# POWER_Manegement.net
KiCad netlist of a schematic drawn in Altium Designer
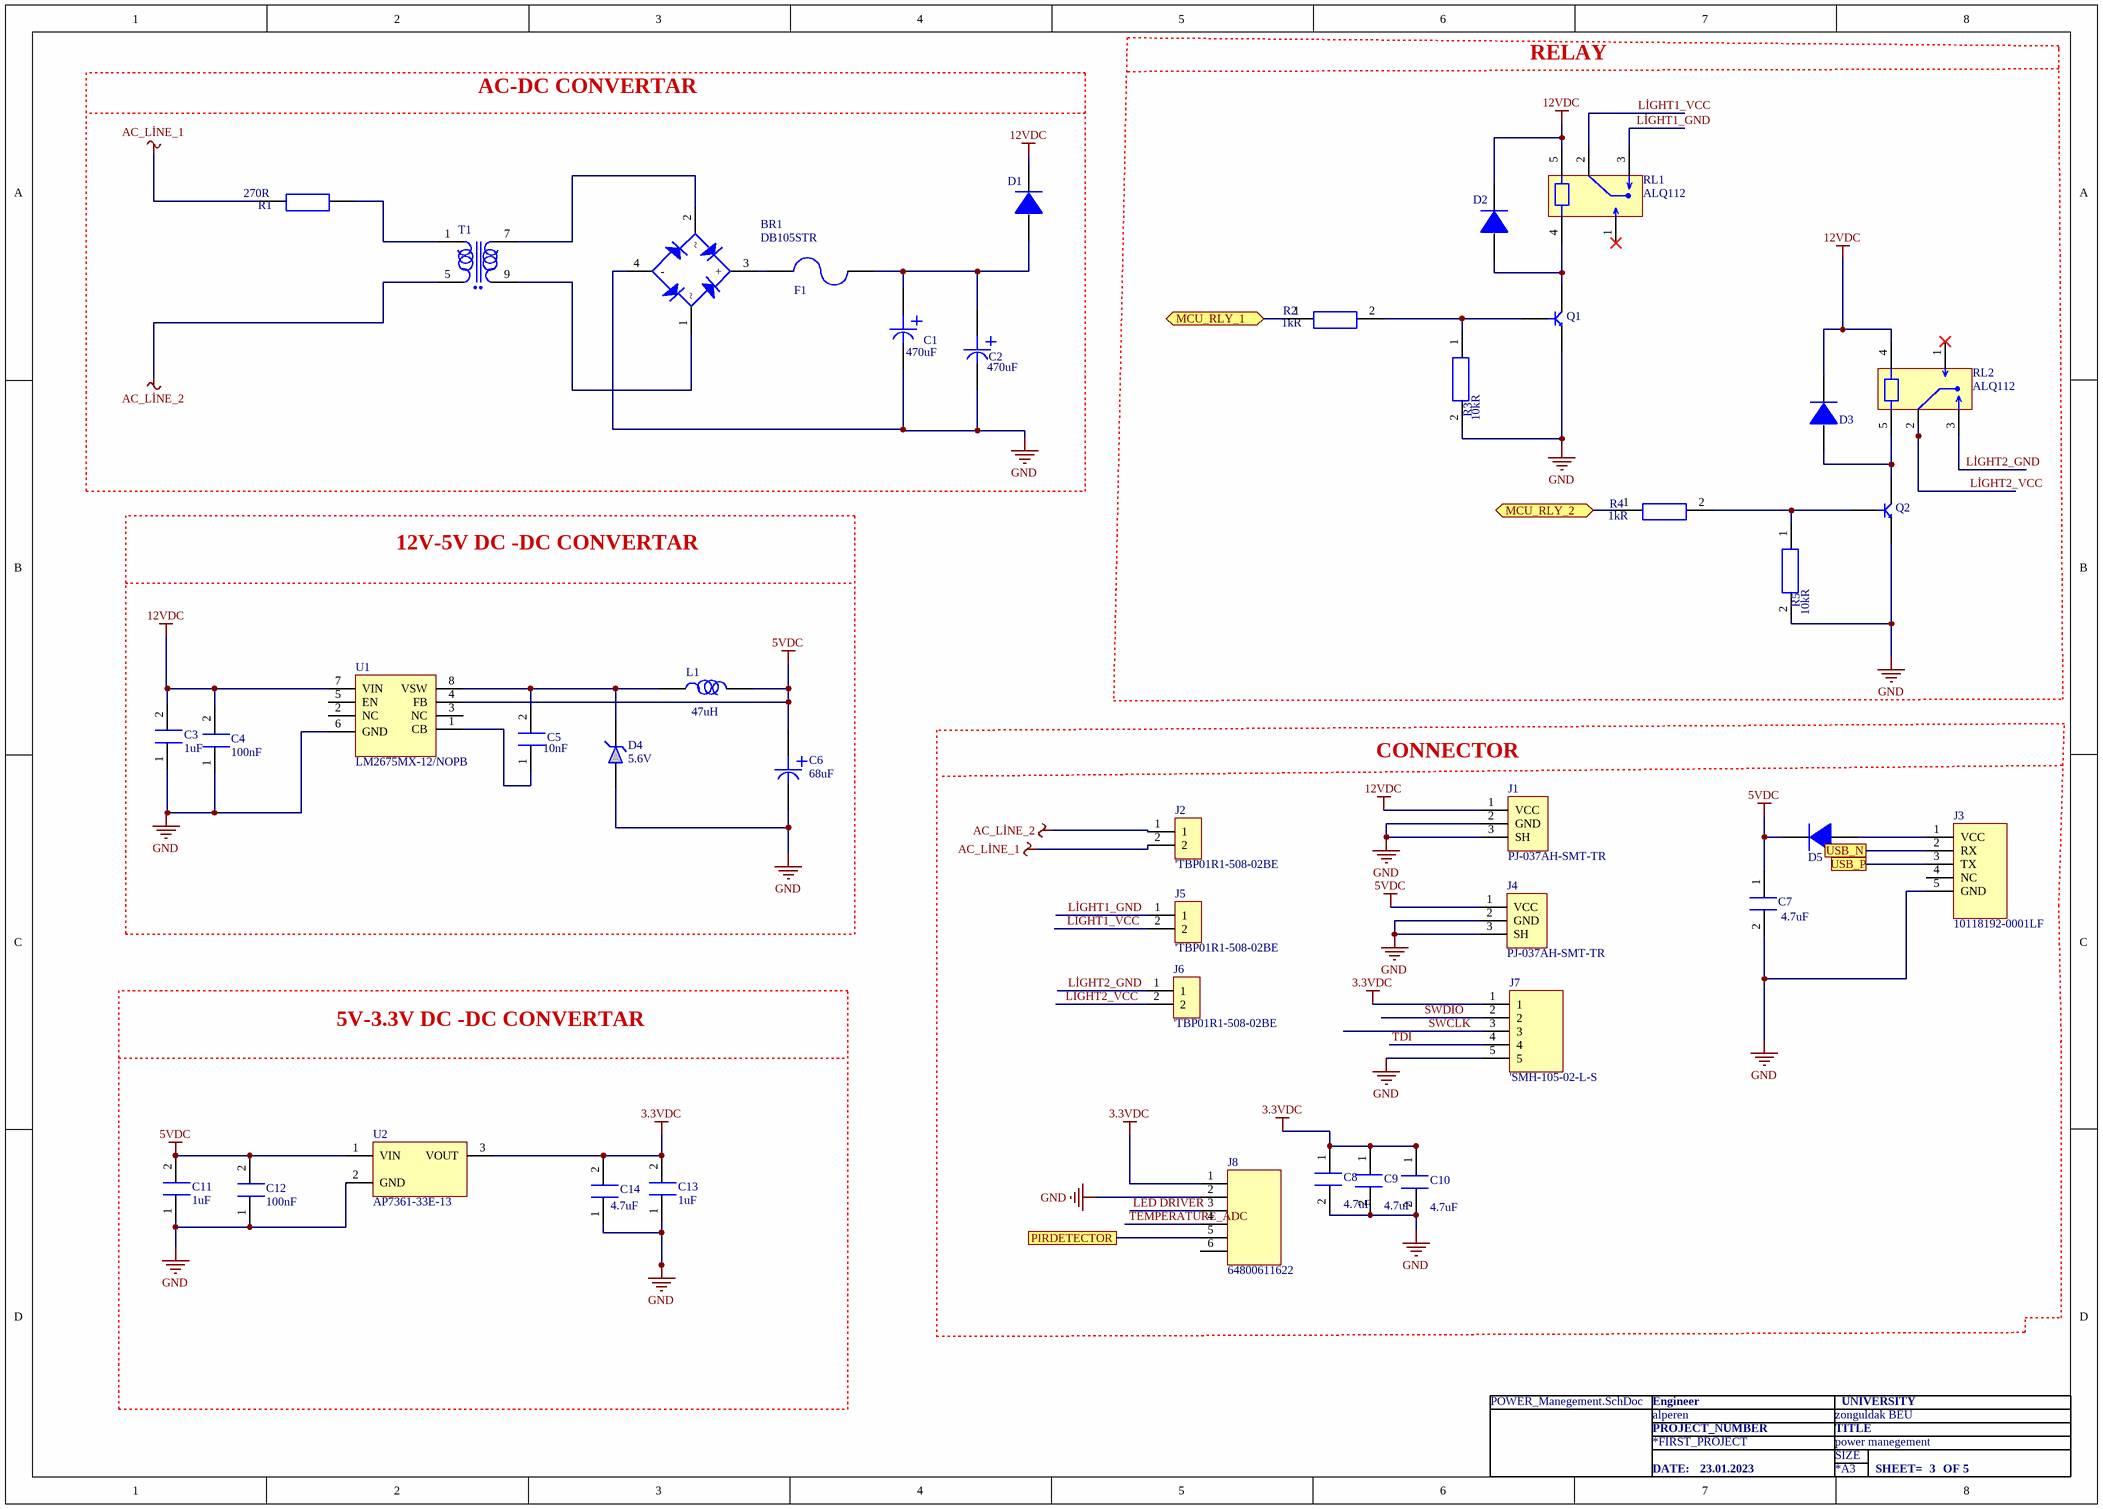
[diagram p0: POWER_Manegement.SchDoc]

(export (version "E")
  (design (tool "Eeschema 10.0.6"))
  (components
    (comp (ref "BR1")
      (value "DB105STR")
      (footprint "DB105STR")
      (description "Bridge Rect 1PHASE 600V 1A Db-s")
      (fields
        (field (name "MANUFACTURER") "Sangdest Microelectronics")
        (field (name "MANUFACTURER PART NUMBER") "DB105S")
      )
      (libsource (lib "first_project_library") (part "DB105STR"))
    )
    (comp (ref "C1")
      (value "ESH477M050AH4AA")
      (footprint "CAP_RADIAL_D10_P5")
      (description "Cap, 470UF, 50V, Alu Elec, Radial")
      (fields
        (field (name "MANUFACTURER") "KEMET")
        (field (name "TOLERANCE") "20%")
        (field (name "CAPACITANCE") "470uF")
      )
      (libsource (lib "first_project_library") (part "ESH477M050AH4AA"))
    )
    (comp (ref "C2")
      (value "ESH477M050AH4AA")
      (footprint "CAP_RADIAL_D10_P5")
      (description "Cap, 470UF, 50V, Alu Elec, Radial")
      (fields
        (field (name "MANUFACTURER") "KEMET")
        (field (name "TOLERANCE") "20%")
        (field (name "CAPACITANCE") "470uF")
      )
      (libsource (lib "first_project_library") (part "ESH477M050AH4AA"))
    )
    (comp (ref "C3")
      (value "CAP CER 1UF 0805")
      (footprint "CAP_0805")
      (description "CAP CER 1UF 25V X5R 0805")
      (fields
        (field (name "MANUFACTURER") "Murata")
        (field (name "MANUFACTURER PART NUMBER") "GRM216R61E105KA12D")
        (field (name "CAPACITANCE") "1uF")
      )
      (libsource (lib "first_project_library") (part "CAP CER 1UF 0805"))
    )
    (comp (ref "C4")
      (value "CAP CF 100NF 0805")
      (footprint "CAP_0805")
      (description "CAP CER 0.1UF 50V X7R 0805")
      (fields
        (field (name "MANUFACTURER") "Samsung")
        (field (name "MANUFACTURER PART NUMBER") "CL21B104KBCNNNC")
        (field (name "CAPACITANCE") "100nF")
      )
      (libsource (lib "first_project_library") (part "CAP CF 100NF 0805"))
    )
    (comp (ref "C5")
      (value "CAP CER 10nF 0603")
      (footprint "CAP_0603")
      (description "Multilayer Ceramic Capacitor, 0.01 F, 10%, X7R, 16 V, 0603 [1608 Metric] RoHS Compliant: Yes")
      (fields
        (field (name "MANUFACTURER") "Walsin Technologies")
        (field (name "MANUFACTURER PART NUMBER") "0603B103K160CT")
        (field (name "CAPACITANCE") "10nF")
      )
      (libsource (lib "first_project_library") (part "CAP CER 10nF 0603"))
    )
    (comp (ref "C6")
      (value "EEV686M035A9HAA")
      (footprint "CAP_EEVseries")
      (description "Cap Aluminum Lytic 68uF 35V 20% (6.3 X 7.7mm) SMD 280mA 2000h 105C T/R")
      (fields
        (field (name "MANUFACTURER") "KEMET")
        (field (name "TOLERANCE") "20%")
        (field (name "CAPACITANCE") "68uF")
        (field (name "THIS PART IS DESIGNED") "alperen")
      )
      (libsource (lib "first_project_library") (part "CAP ALU 68uF"))
    )
    (comp (ref "C7")
      (value "CAP CER 4.7uF 0805")
      (footprint "CAP_0805")
      (description "CAP CER 4.7UF 25V X5R 0805")
      (fields
        (field (name "MANUFACTURER") "Samsung")
        (field (name "MANUFACTURER PART NUMBER") "CL21A475KAQNNNE")
        (field (name "CAPACITANCE") "4.7uF")
      )
      (libsource (lib "first_project_library") (part "CAP CER 4.7uF 0805"))
    )
    (comp (ref "C8")
      (value "CAP CER 4.7uF 0805")
      (footprint "CAP_0805")
      (description "CAP CER 4.7UF 25V X5R 0805")
      (fields
        (field (name "MANUFACTURER") "Samsung")
        (field (name "MANUFACTURER PART NUMBER") "CL21A475KAQNNNE")
        (field (name "CAPACITANCE") "4.7uF")
      )
      (libsource (lib "first_project_library") (part "CAP CER 4.7uF 0805"))
    )
    (comp (ref "C9")
      (value "CAP CER 4.7uF 0805")
      (footprint "CAP_0805")
      (description "CAP CER 4.7UF 25V X5R 0805")
      (fields
        (field (name "MANUFACTURER") "Samsung")
        (field (name "MANUFACTURER PART NUMBER") "CL21A475KAQNNNE")
        (field (name "CAPACITANCE") "4.7uF")
      )
      (libsource (lib "first_project_library") (part "CAP CER 4.7uF 0805"))
    )
    (comp (ref "C10")
      (value "CAP CER 4.7uF 0805")
      (footprint "CAP_0805")
      (description "CAP CER 4.7UF 25V X5R 0805")
      (fields
        (field (name "MANUFACTURER") "Samsung")
        (field (name "MANUFACTURER PART NUMBER") "CL21A475KAQNNNE")
        (field (name "CAPACITANCE") "4.7uF")
      )
      (libsource (lib "first_project_library") (part "CAP CER 4.7uF 0805"))
    )
    (comp (ref "C11")
      (value "CAP CER 1UF 0805")
      (footprint "CAP_0805")
      (description "CAP CER 1UF 25V X5R 0805")
      (fields
        (field (name "MANUFACTURER") "Murata")
        (field (name "MANUFACTURER PART NUMBER") "GRM216R61E105KA12D")
        (field (name "CAPACITANCE") "1uF")
      )
      (libsource (lib "first_project_library") (part "CAP CER 1UF 0805"))
    )
    (comp (ref "C12")
      (value "CAP CF 100NF 0805")
      (footprint "CAP_0805")
      (description "CAP CER 0.1UF 50V X7R 0805")
      (fields
        (field (name "MANUFACTURER") "Samsung")
        (field (name "MANUFACTURER PART NUMBER") "CL21B104KBCNNNC")
        (field (name "CAPACITANCE") "100nF")
      )
      (libsource (lib "first_project_library") (part "CAP CF 100NF 0805"))
    )
    (comp (ref "C13")
      (value "CAP CER 1UF 0805")
      (footprint "CAP_0805")
      (description "CAP CER 1UF 25V X5R 0805")
      (fields
        (field (name "MANUFACTURER") "Murata")
        (field (name "MANUFACTURER PART NUMBER") "GRM216R61E105KA12D")
        (field (name "CAPACITANCE") "1uF")
      )
      (libsource (lib "first_project_library") (part "CAP CER 1UF 0805"))
    )
    (comp (ref "C14")
      (value "CAP CER 4.7uF 0805")
      (footprint "CAP_0805")
      (description "CAP CER 4.7UF 25V X5R 0805")
      (fields
        (field (name "MANUFACTURER") "Samsung")
        (field (name "MANUFACTURER PART NUMBER") "CL21A475KAQNNNE")
        (field (name "CAPACITANCE") "4.7uF")
      )
      (libsource (lib "first_project_library") (part "CAP CER 4.7uF 0805"))
    )
    (comp (ref "D1")
      (value "1N4148WS")
      (footprint "SOD323")
      (description "VR=75V IF=150mA Trr=4ns P=200mW")
      (fields (field (name "MANUFACTURER") "ON Semiconductor / Fairchild"))
      (libsource (lib "first_project_library") (part "1N4148WS"))
    )
    (comp (ref "D2")
      (value "1N4148WS")
      (footprint "SOD323")
      (description "VR=75V IF=150mA Trr=4ns P=200mW")
      (fields (field (name "MANUFACTURER") "ON Semiconductor / Fairchild"))
      (libsource (lib "first_project_library") (part "1N4148WS"))
    )
    (comp (ref "D3")
      (value "1N4148WS")
      (footprint "SOD323")
      (description "VR=75V IF=150mA Trr=4ns P=200mW")
      (fields (field (name "MANUFACTURER") "ON Semiconductor / Fairchild"))
      (libsource (lib "first_project_library") (part "1N4148WS"))
    )
    (comp (ref "D4")
      (value "1SMB5919BT3G")
      (footprint "SMB")
      (description "Vz=5.6V 5.32V~5.88V Izt=66.9mA")
      (fields
        (field (name "MANUFACTURER") "ON Semiconductor")
        (field (name "TOLERANCE") "5%")
        (field (name "ZENER VOLTAGE") "5.6V")
      )
      (libsource (lib "first_project_library") (part "1SMB5919BT3G"))
    )
    (comp (ref "D5")
      (value "1N4148WS")
      (footprint "SOD323")
      (description "VR=75V IF=150mA Trr=4ns P=200mW")
      (fields (field (name "MANUFACTURER") "ON Semiconductor / Fairchild"))
      (libsource (lib "first_project_library") (part "1N4148WS"))
    )
    (comp (ref "F1")
      (value "FUSE 3413.0216.22")
      (footprint "FUSE 3413.0216.22")
      (description "Fuse Chip Fast Acting 1A 32V SMD Solder Pad 1206 Glass T/R VDE/cULus")
      (fields
        (field (name "MANUFACTURER") "Schurter")
        (field (name "MANUFACTURER PART NUMBER") "3413.0216.22")
      )
      (libsource (lib "first_project_library") (part "FUSE 3413.0216.22"))
    )
    (comp (ref "J1")
      (value "PJ-037AH-SMT-TR")
      (footprint "JACK")
      (description "2.0 x 6.3 mm, 5.0 A, Horizontal, Surface Mount (SMT), Dc Power Jack Connector")
      (fields (field (name "MANUFACTURER") "CUI") (field (name "THIS PART IS DESIGNED") "alperen"))
      (libsource (lib "first_project_library") (part "PJ-037AH-SMT-TR"))
    )
    (comp (ref "J2")
      (value "'TBP01R1-508-02BE")
      (footprint "'TBP01R1-508")
      (description "2~24 Poles, Pluggable, Receptacle, Horizontal, 5.08 Pitch, Terminal Block Connector")
      (fields
        (field (name "MANUFACTURER") "CUI Devices")
        (field (name "MANUFACTURER PART NUMBER") "TBP01R1-508-02BE")
      )
      (libsource (lib "first_project_library") (part "'TBP01R1-508-02BE"))
    )
    (comp (ref "J3")
      (value "10118192-0001LF")
      (footprint "MICRO_B_USB")
      (description "CONN USB MICRO B RECPT SMT R/A")
      (fields
        (field (name "MANUFACTURER") "Amphenol ICC / FCI")
        (field (name "THIS PART IS DESIGNED") "alperen")
      )
      (libsource (lib "first_project_library") (part "Micro B USB connector"))
    )
    (comp (ref "J4")
      (value "PJ-037AH-SMT-TR")
      (footprint "JACK")
      (description "2.0 x 6.3 mm, 5.0 A, Horizontal, Surface Mount (SMT), Dc Power Jack Connector")
      (fields (field (name "MANUFACTURER") "CUI") (field (name "THIS PART IS DESIGNED") "alperen"))
      (libsource (lib "first_project_library") (part "PJ-037AH-SMT-TR"))
    )
    (comp (ref "J5")
      (value "'TBP01R1-508-02BE")
      (footprint "'TBP01R1-508")
      (description "2~24 Poles, Pluggable, Receptacle, Horizontal, 5.08 Pitch, Terminal Block Connector")
      (fields
        (field (name "MANUFACTURER") "CUI Devices")
        (field (name "MANUFACTURER PART NUMBER") "TBP01R1-508-02BE")
      )
      (libsource (lib "first_project_library") (part "'TBP01R1-508-02BE"))
    )
    (comp (ref "J6")
      (value "'TBP01R1-508-02BE")
      (footprint "'TBP01R1-508")
      (description "2~24 Poles, Pluggable, Receptacle, Horizontal, 5.08 Pitch, Terminal Block Connector")
      (fields
        (field (name "MANUFACTURER") "CUI Devices")
        (field (name "MANUFACTURER PART NUMBER") "TBP01R1-508-02BE")
      )
      (libsource (lib "first_project_library") (part "'TBP01R1-508-02BE"))
    )
    (comp (ref "J7")
      (value "'SMH-105-02-L-S")
      (footprint "PINHEADER 1X5_RA")
      (description ".100 C.L. HORIZONTAL SMT SOCKET")
      (fields
        (field (name "MANUFACTURER") "Samtec")
        (field (name "MANUFACTURER PART NUMBER") "SMH-105-02-L-S")
        (field (name "THIS PART IS DESIGNED") "alperen")
      )
      (libsource (lib "first_project_library") (part "SMH-105-02-L-S"))
    )
    (comp (ref "J8")
      (value "64800611622")
      (footprint "64800611622")
      (description "Conn, Header, 6POS, 1ROW, 1.5MM;")
      (fields
        (field (name "MANUFACTURER") "Wurth Electronics")
        (field (name "THIS PART IS DESIGNED") "alperen")
      )
      (libsource (lib "first_project_library") (part "64800611622_CONN_6PİN"))
    )
    (comp (ref "L1")
      (value "78438335470")
      (footprint "IND_1212")
      (description "Fixed Ind 47UH 390MA 2.3 Ohm SMD")
      (fields
        (field (name "MANUFACTURER") "Wurth Electronics")
        (field (name "TOLERANCE") "30%")
        (field (name "INDUCTANCE") "47uH")
      )
      (libsource (lib "first_project_library") (part "IND 47uH"))
    )
    (comp (ref "Q1")
      (value "MMBT3904-7-F")
      (footprint "SOT-23F")
      (description "NPN Ic=200mA Vceo=40V hfe=100~300 fT=310MHz P=300mW SOT-23")
      (fields (field (name "MANUFACTURER") "Diodes Zetex") (field (name "THIS PART IS DESIGNED") "alperen"))
      (libsource (lib "first_project_library") (part "MMBT3904-7-F"))
    )
    (comp (ref "Q2")
      (value "MMBT3904-7-F")
      (footprint "SOT-23F")
      (description "NPN Ic=200mA Vceo=40V hfe=100~300 fT=310MHz P=300mW SOT-23")
      (fields (field (name "MANUFACTURER") "Diodes Zetex") (field (name "THIS PART IS DESIGNED") "alperen"))
      (libsource (lib "first_project_library") (part "MMBT3904-7-F"))
    )
    (comp (ref "R1")
      (value "RES_AXIAL_W")
      (footprint "RES_AXIAL_W")
      (description "Resistor 5 Watt Cermet Wirewound Flameproof .27 Ohm 5% Axial Lead")
      (fields
        (field (name "MANUFACTURER") "NTE Electronics")
        (field (name "MANUFACTURER PART NUMBER") "5WD27")
        (field (name "RESISTANCE") "270R")
      )
      (libsource (lib "first_project_library") (part "RES_AXIAL_W"))
    )
    (comp (ref "R2")
      (value "RES_1KOHM")
      (footprint "RES_0603")
      (description "Res Thin Film 0603 1K Ohm 0.1% 1/10W ±25ppm/°C Molded SMD SMD Punched Carrier T/R")
      (fields
        (field (name "MANUFACTURER") "Panasonic")
        (field (name "MANUFACTURER PART NUMBER") "ERA-3AEB102V")
        (field (name "RESISTANCE") "1kR")
        (field (name "THIS PART IS DESIGNED") "alperen")
      )
      (libsource (lib "first_project_library") (part "RES_1KOHM"))
    )
    (comp (ref "R3")
      (value "RES 10KOHM%1 0603")
      (footprint "RES_0603")
      (description "RES SMD 10K OHM 1% 1/10W 0603")
      (fields
        (field (name "MANUFACTURER") "Yageo")
        (field (name "MANUFACTURER PART NUMBER") "RC0603FR-0710KL")
        (field (name "RESISTANCE") "10kR")
      )
      (libsource (lib "first_project_library") (part "RES 10KOHM 0603"))
    )
    (comp (ref "R4")
      (value "RES_1KOHM")
      (footprint "RES_0603")
      (description "Res Thin Film 0603 1K Ohm 0.1% 1/10W ±25ppm/°C Molded SMD SMD Punched Carrier T/R")
      (fields
        (field (name "MANUFACTURER") "Panasonic")
        (field (name "MANUFACTURER PART NUMBER") "ERA-3AEB102V")
        (field (name "RESISTANCE") "1kR")
        (field (name "THIS PART IS DESIGNED") "alperen")
      )
      (libsource (lib "first_project_library") (part "RES_1KOHM"))
    )
    (comp (ref "R5")
      (value "RES 10KOHM%1 0603")
      (footprint "RES_0603")
      (description "RES SMD 10K OHM 1% 1/10W 0603")
      (fields
        (field (name "MANUFACTURER") "Yageo")
        (field (name "MANUFACTURER PART NUMBER") "RC0603FR-0710KL")
        (field (name "RESISTANCE") "10kR")
      )
      (libsource (lib "first_project_library") (part "RES 10KOHM 0603"))
    )
    (comp (ref "RL1")
      (value "ALQ112")
      (footprint "ALQ112")
      (description "RELAY GEN PURPOSE SPDT 10A 12V")
      (fields (field (name "MANUFACTURER") "Panasonic"))
      (libsource (lib "") (part "ALQ112_1"))
    )
    (comp (ref "RL2")
      (value "ALQ112")
      (footprint "ALQ112")
      (description "RELAY GEN PURPOSE SPDT 10A 12V")
      (fields (field (name "MANUFACTURER") "Panasonic"))
      (libsource (lib "first_project_library") (part "ALQ112"))
    )
    (comp (ref "T1")
      (value "BV302S12010-ZU")
      (footprint "BV302S12010-ZU")
      (description "BV Series Single 230 Vin Single Out 125 mA Sealed Power Transformer")
      (fields
        (field (name "MANUFACTURER") "Zettler Magnetics")
        (field (name "MANUFACTURER PART NUMBER") "BV302S12015-ZU")
      )
      (libsource (lib "first_project_library") (part "BV302S12010-ZU"))
    )
    (comp (ref "U1")
      (value "LM2675MX-12/NOPB")
      (footprint "SOIC8")
      (description "SIMPLE SWITCHER® 6.5V to 40V, 1A Low Component Count Step-Down Regulator 8-SOIC -40 to 125")
      (fields (field (name "MANUFACTURER") "TI National Semiconductor"))
      (libsource (lib "first_project_library") (part "LM2675MX-12/NOPB"))
    )
    (comp (ref "U2")
      (value "AP7361-33E-13")
      (footprint "SOT-223")
      (description "AP7361 Series 3.3 V 1 A Low SMT Dropout Fixed-Mode Regulator - SOT-223")
      (fields (field (name "MANUFACTURER") "Diodes"))
      (libsource (lib "first_project_library") (part "AP7361-33E-13"))
    )
  )
  (nets
    (net (code "1") (name "/LED DRIVER") (class "Default")
      (node (ref "J8") (pin "3") (pinfunction "TX_3") (pintype "passive"))
    )
    (net (code "2") (name "/LİGHT1_GND") (class "Default")
      (node (ref "J5") (pin "1") (pinfunction "1_1") (pintype "passive"))
      (node (ref "RL1") (pin "3") (pinfunction "3_3") (pintype "passive"))
    )
    (net (code "3") (name "/LİGHT1_VCC") (class "Default")
      (node (ref "J5") (pin "2") (pinfunction "2_2") (pintype "passive"))
      (node (ref "RL1") (pin "2") (pinfunction "2_2") (pintype "passive"))
    )
    (net (code "4") (name "/LİGHT2_GND") (class "Default")
      (node (ref "J6") (pin "1") (pinfunction "1_1") (pintype "passive"))
      (node (ref "RL2") (pin "3") (pinfunction "3_3") (pintype "passive"))
    )
    (net (code "5") (name "/LİGHT2_VCC") (class "Default")
      (node (ref "J6") (pin "2") (pinfunction "2_2") (pintype "passive"))
      (node (ref "RL2") (pin "2") (pinfunction "2_2") (pintype "passive"))
    )
    (net (code "6") (name "/MCU_RLY_1") (class "Default") (node (ref "R2") (pin "1") (pintype "passive")))
    (net (code "7") (name "/MCU_RLY_2") (class "Default") (node (ref "R4") (pin "1") (pintype "passive")))
    (net (code "8") (name "/PIRDETECTOR") (class "Default")
      (node (ref "J8") (pin "5") (pinfunction "GND_5") (pintype "passive"))
    )
    (net (code "9") (name "/SWCLK") (class "Default")
      (node (ref "J7") (pin "3") (pinfunction "3_3") (pintype "passive"))
    )
    (net (code "10") (name "/SWDIO") (class "Default")
      (node (ref "J7") (pin "2") (pinfunction "2_2") (pintype "passive"))
    )
    (net (code "11") (name "/TDI") (class "Default")
      (node (ref "J7") (pin "4") (pinfunction "4_4") (pintype "passive"))
    )
    (net (code "12") (name "/TEMPERATURE_ADC") (class "Default")
      (node (ref "J8") (pin "4") (pinfunction "NC_4") (pintype "passive"))
    )
    (net (code "13") (name "/USB_N") (class "Default")
      (node (ref "J3") (pin "2") (pinfunction "RX_2") (pintype "passive"))
    )
    (net (code "14") (name "/USB_P") (class "Default")
      (node (ref "J3") (pin "3") (pinfunction "TX_3") (pintype "passive"))
    )
    (net (code "15") (name "3.3VDC") (class "Default")
      (node (ref "C10") (pin "1") (pintype "passive"))
      (node (ref "C13") (pin "2") (pintype "passive"))
      (node (ref "C14") (pin "2") (pintype "passive"))
      (node (ref "C8") (pin "1") (pintype "passive"))
      (node (ref "C9") (pin "1") (pintype "passive"))
      (node (ref "J7") (pin "1") (pinfunction "1_1") (pintype "passive"))
      (node (ref "J8") (pin "1") (pinfunction "VCC_1") (pintype "passive"))
      (node (ref "U2") (pin "3") (pinfunction "VOUT_3") (pintype "passive"))
    )
    (net (code "16") (name "5VDC") (class "Default")
      (node (ref "C11") (pin "2") (pintype "passive"))
      (node (ref "C12") (pin "2") (pintype "passive"))
      (node (ref "C6") (pin "1") (pintype "passive"))
      (node (ref "C7") (pin "1") (pintype "passive"))
      (node (ref "D5") (pin "1") (pintype "passive"))
      (node (ref "J4") (pin "1") (pinfunction "VCC_1") (pintype "power_in"))
      (node (ref "L1") (pin "2") (pintype "passive"))
      (node (ref "U1") (pin "4") (pinfunction "FB_4") (pintype "passive"))
      (node (ref "U2") (pin "1") (pinfunction "VIN_1") (pintype "passive"))
    )
    (net (code "17") (name "12VDC") (class "Default")
      (node (ref "C3") (pin "2") (pintype "passive"))
      (node (ref "C4") (pin "2") (pintype "passive"))
      (node (ref "D1") (pin "1") (pintype "passive"))
      (node (ref "D2") (pin "1") (pintype "passive"))
      (node (ref "D3") (pin "1") (pintype "passive"))
      (node (ref "J1") (pin "1") (pinfunction "VCC_1") (pintype "power_in"))
      (node (ref "RL1") (pin "5") (pinfunction "5_5") (pintype "passive"))
      (node (ref "RL2") (pin "4") (pinfunction "4_4") (pintype "passive"))
      (node (ref "U1") (pin "7") (pinfunction "VIN_7") (pintype "passive"))
    )
    (net (code "18") (name "AC_LİNE_1") (class "Default")
      (node (ref "J2") (pin "2") (pinfunction "2_2") (pintype "passive"))
      (node (ref "R1") (pin "1") (pintype "passive"))
    )
    (net (code "19") (name "AC_LİNE_2") (class "Default")
      (node (ref "J2") (pin "1") (pinfunction "1_1") (pintype "passive"))
      (node (ref "T1") (pin "5") (pinfunction "3_5") (pintype "passive"))
    )
    (net (code "20") (name "GND") (class "Default")
      (node (ref "BR1") (pin "4") (pinfunction "-_4") (pintype "passive"))
      (node (ref "C1") (pin "2") (pintype "passive"))
      (node (ref "C10") (pin "2") (pintype "passive"))
      (node (ref "C11") (pin "1") (pintype "passive"))
      (node (ref "C12") (pin "1") (pintype "passive"))
      (node (ref "C13") (pin "1") (pintype "passive"))
      (node (ref "C14") (pin "1") (pintype "passive"))
      (node (ref "C2") (pin "2") (pintype "passive"))
      (node (ref "C3") (pin "1") (pintype "passive"))
      (node (ref "C4") (pin "1") (pintype "passive"))
      (node (ref "C6") (pin "2") (pintype "passive"))
      (node (ref "C7") (pin "2") (pintype "passive"))
      (node (ref "C8") (pin "2") (pintype "passive"))
      (node (ref "C9") (pin "2") (pintype "passive"))
      (node (ref "D4") (pin "C") (pintype "passive"))
      (node (ref "J1") (pin "2") (pinfunction "GND_2") (pintype "power_in"))
      (node (ref "J1") (pin "3") (pinfunction "SH_3") (pintype "power_in"))
      (node (ref "J3") (pin "5") (pinfunction "GND_5") (pintype "passive"))
      (node (ref "J4") (pin "2") (pinfunction "GND_2") (pintype "power_in"))
      (node (ref "J4") (pin "3") (pinfunction "SH_3") (pintype "power_in"))
      (node (ref "J7") (pin "5") (pinfunction "5_5") (pintype "passive"))
      (node (ref "J8") (pin "2") (pinfunction "RX_2") (pintype "passive"))
      (node (ref "Q1") (pin "2") (pinfunction "E_2") (pintype "passive"))
      (node (ref "Q2") (pin "2") (pinfunction "E_2") (pintype "passive"))
      (node (ref "R3") (pin "2") (pintype "passive"))
      (node (ref "R5") (pin "2") (pintype "passive"))
      (node (ref "U1") (pin "6") (pinfunction "GND_6") (pintype "passive"))
      (node (ref "U2") (pin "2") (pinfunction "GND_2") (pintype "passive"))
    )
    (net (code "21") (name "Net-(BR1-+)") (class "Default")
      (node (ref "BR1") (pin "3") (pinfunction "+_3") (pintype "passive"))
      (node (ref "F1") (pin "1") (pintype "passive"))
    )
    (net (code "22") (name "Net-(C1-Pad1)") (class "Default")
      (node (ref "C1") (pin "1") (pintype "passive"))
      (node (ref "C2") (pin "1") (pintype "passive"))
      (node (ref "D1") (pin "2") (pintype "passive"))
      (node (ref "F1") (pin "2") (pintype "passive"))
    )
    (net (code "23") (name "Net-(J3-VCC)") (class "Default")
      (node (ref "D5") (pin "2") (pintype "passive"))
      (node (ref "J3") (pin "1") (pinfunction "VCC_1") (pintype "passive"))
    )
    (net (code "24") (name "Net-(Q1-B)") (class "Default")
      (node (ref "Q1") (pin "1") (pinfunction "B_1") (pintype "passive"))
      (node (ref "R2") (pin "2") (pintype "passive"))
      (node (ref "R3") (pin "1") (pintype "passive"))
    )
    (net (code "25") (name "Net-(Q1-C)") (class "Default")
      (node (ref "D2") (pin "2") (pintype "passive"))
      (node (ref "Q1") (pin "3") (pinfunction "C_3") (pintype "passive"))
      (node (ref "RL1") (pin "4") (pinfunction "4_4") (pintype "passive"))
    )
    (net (code "26") (name "Net-(Q2-B)") (class "Default")
      (node (ref "Q2") (pin "1") (pinfunction "B_1") (pintype "passive"))
      (node (ref "R4") (pin "2") (pintype "passive"))
      (node (ref "R5") (pin "1") (pintype "passive"))
    )
    (net (code "27") (name "Net-(Q2-C)") (class "Default")
      (node (ref "D3") (pin "2") (pintype "passive"))
      (node (ref "Q2") (pin "3") (pinfunction "C_3") (pintype "passive"))
      (node (ref "RL2") (pin "5") (pinfunction "5_5") (pintype "passive"))
    )
    (net (code "28") (name "Net-(R1-Pad2)") (class "Default")
      (node (ref "R1") (pin "2") (pintype "passive"))
      (node (ref "T1") (pin "1") (pinfunction "1_1") (pintype "passive"))
    )
    (net (code "29") (name "Net-(T1-2)") (class "Default")
      (node (ref "BR1") (pin "2") (pinfunction "~_2") (pintype "passive"))
      (node (ref "T1") (pin "7") (pinfunction "2_7") (pintype "passive"))
    )
    (net (code "30") (name "Net-(T1-4)") (class "Default")
      (node (ref "BR1") (pin "1") (pinfunction "~_1") (pintype "passive"))
      (node (ref "T1") (pin "9") (pinfunction "4_9") (pintype "passive"))
    )
    (net (code "31") (name "Net-(U1-CB)") (class "Default")
      (node (ref "C5") (pin "1") (pintype "passive"))
      (node (ref "U1") (pin "1") (pinfunction "CB_1") (pintype "passive"))
    )
    (net (code "32") (name "Net-(U1-VSW)") (class "Default")
      (node (ref "C5") (pin "2") (pintype "passive"))
      (node (ref "D4") (pin "A") (pintype "passive"))
      (node (ref "L1") (pin "1") (pintype "passive"))
      (node (ref "U1") (pin "8") (pinfunction "VSW_8") (pintype "passive"))
    )
    (net (code "33") (name "unconnected-(J3-NC-Pad4)") (class "Default")
      (node (ref "J3") (pin "4") (pinfunction "NC_4") (pintype "passive"))
    )
    (net (code "34") (name "unconnected-(J8-GND-Pad6)") (class "Default")
      (node (ref "J8") (pin "6") (pinfunction "GND_6") (pintype "passive"))
    )
    (net (code "35") (name "unconnected-(RL1-Pad1)") (class "Default")
      (node (ref "RL1") (pin "1") (pinfunction "1_1") (pintype "passive+no_connect"))
    )
    (net (code "36") (name "unconnected-(RL2-Pad1)") (class "Default")
      (node (ref "RL2") (pin "1") (pinfunction "1_1") (pintype "passive+no_connect"))
    )
    (net (code "37") (name "unconnected-(U1-EN-Pad5)") (class "Default")
      (node (ref "U1") (pin "5") (pinfunction "EN_5") (pintype "passive"))
    )
    (net (code "38") (name "unconnected-(U1-NC-Pad2)") (class "Default")
      (node (ref "U1") (pin "2") (pinfunction "NC_2") (pintype "passive"))
    )
    (net (code "39") (name "unconnected-(U1-NC-Pad3)") (class "Default")
      (node (ref "U1") (pin "3") (pinfunction "NC_3") (pintype "passive"))
    )
  )
)
